# Schematic.net
KiCad netlist of a schematic drawn in Altium Designer
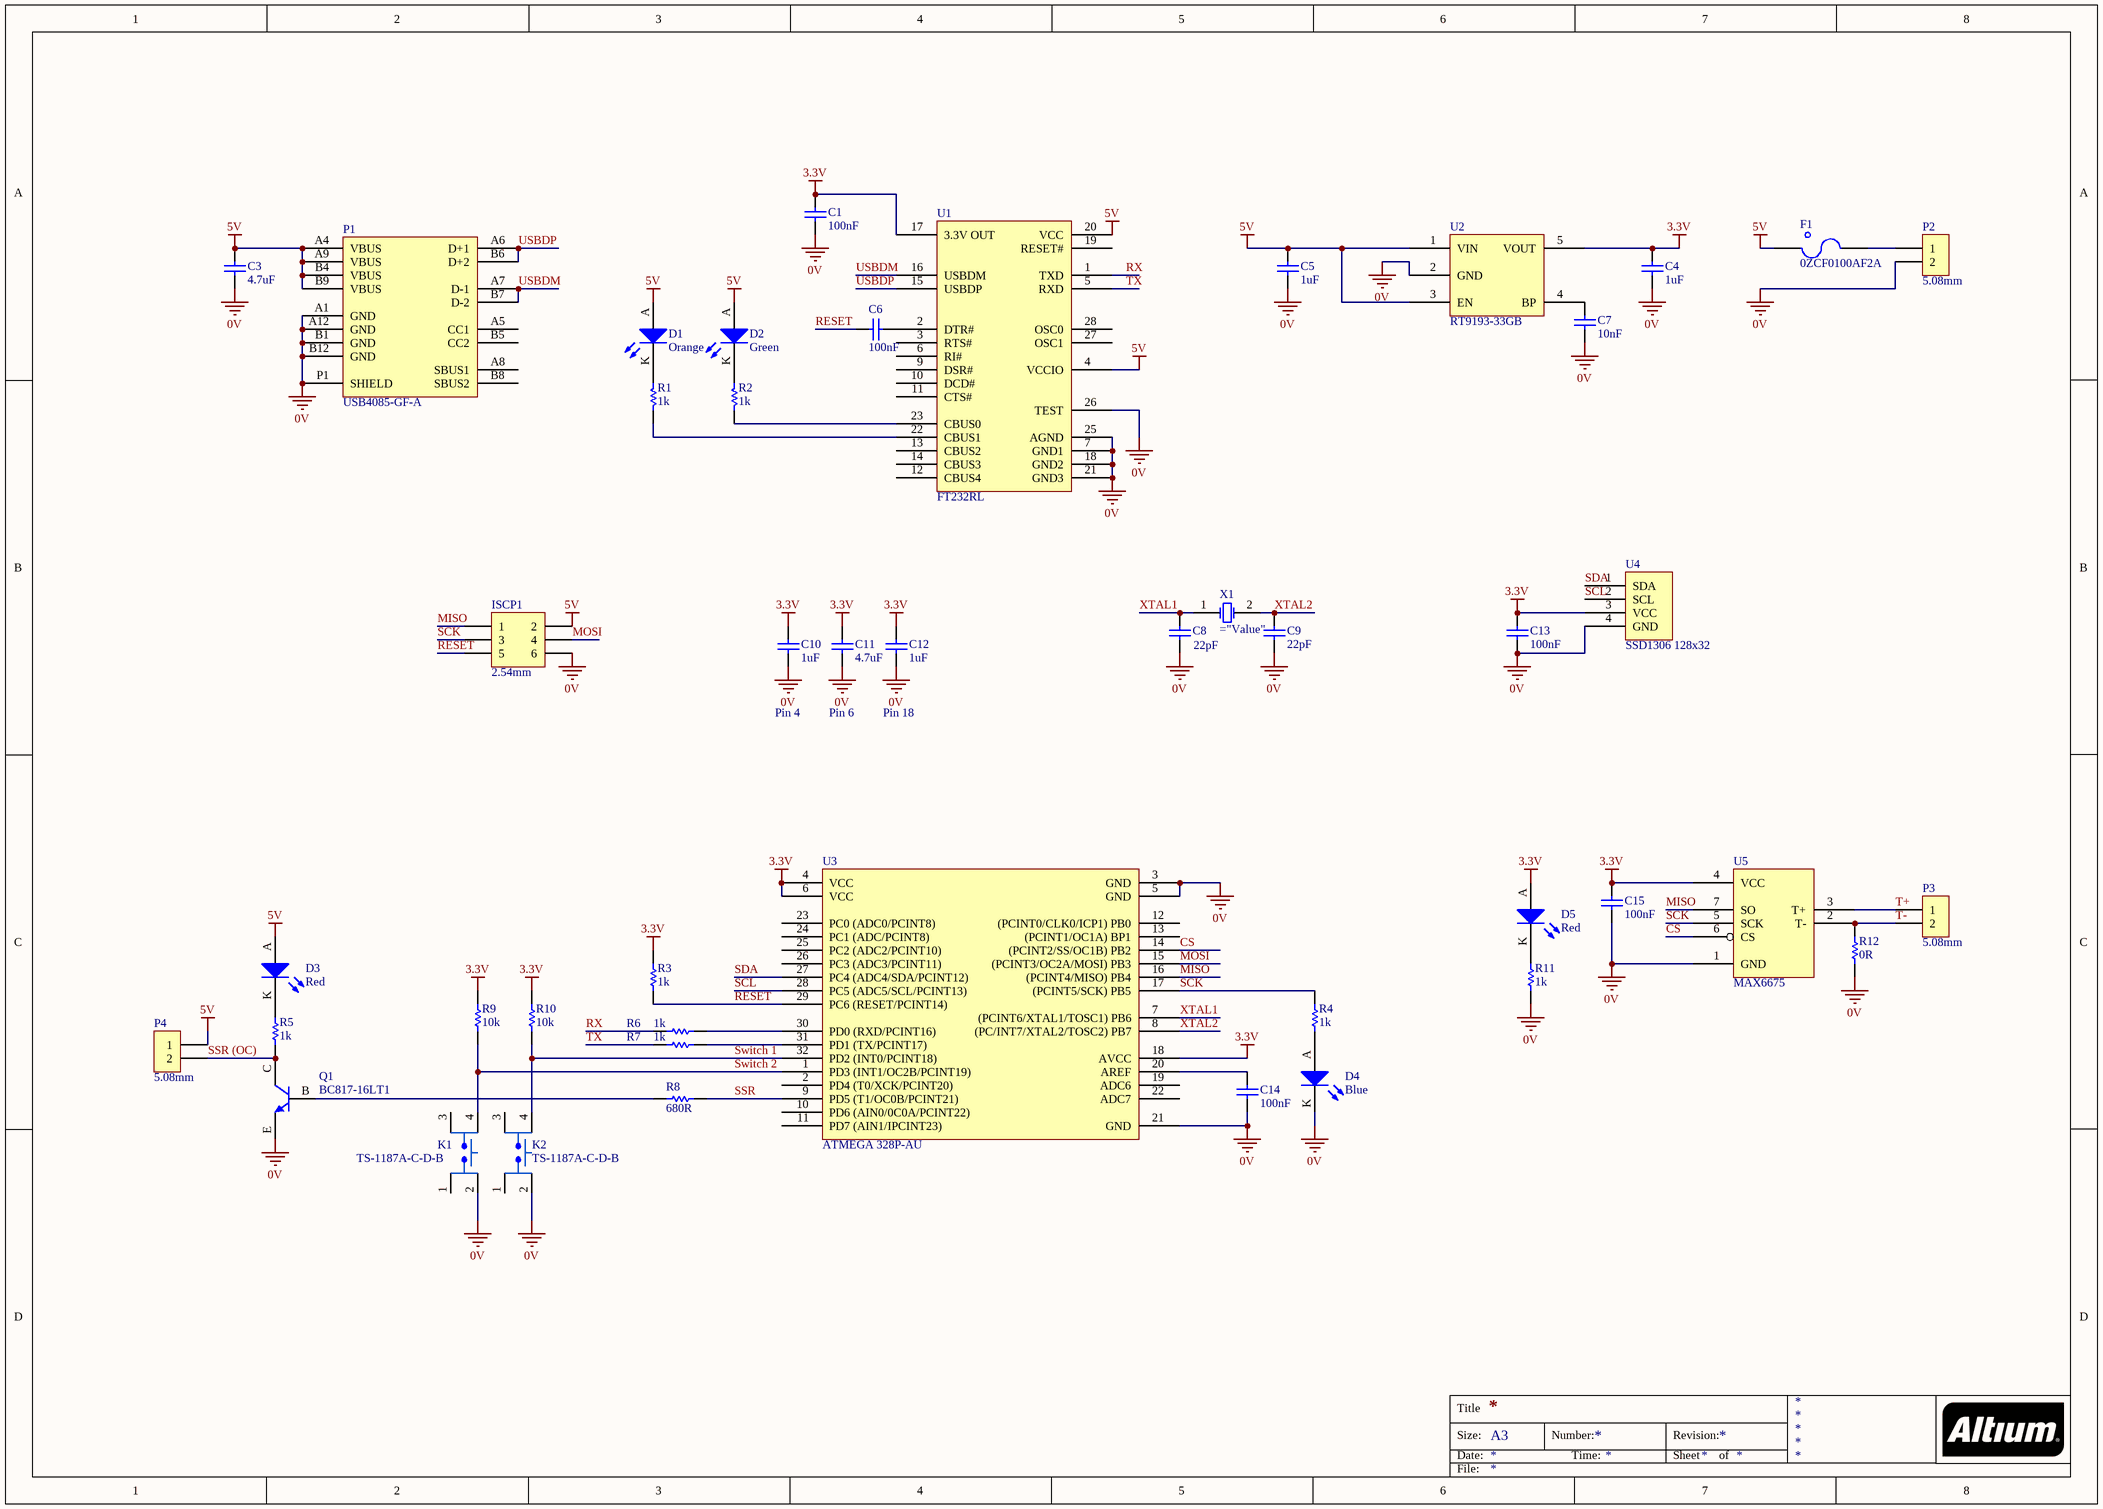
[diagram p0: Schematic.SchDoc]

(export (version "E")
  (design (tool "Eeschema 10.0.6"))
  (components
    (comp (ref "C1")
      (value "100nF")
      (footprint "0805")
      (fields
        (field (name "PART NUMBER") "GCM21BR71H104KA37L")
        (field (name "TOLERANCE") "±10%")
        (field (name "MANUFACTURER") "muRata")
      )
      (libsource (lib "ts_20-standard-library") (part "Capacitor"))
    )
    (comp (ref "C3")
      (value "4.7uF")
      (footprint "0805")
      (fields
        (field (name "PART NUMBER") "GCM21BR61A475KA37L")
        (field (name "TOLERANCE") "10%")
        (field (name "MANUFACTURER") "muRata")
      )
      (libsource (lib "ts_20-standard-library") (part "Capacitor"))
    )
    (comp (ref "C4")
      (value "1uF")
      (footprint "0805")
      (fields
        (field (name "PART NUMBER") "AC0805KKX7R8BB105")
        (field (name "TOLERANCE") "10%")
        (field (name "MANUFACTURER") "YAGEO")
      )
      (libsource (lib "ts_20-standard-library") (part "Capacitor"))
    )
    (comp (ref "C5")
      (value "1uF")
      (footprint "0805")
      (fields
        (field (name "PART NUMBER") "AC0805KKX7R8BB105")
        (field (name "TOLERANCE") "10%")
        (field (name "MANUFACTURER") "YAGEO")
      )
      (libsource (lib "ts_20-standard-library") (part "Capacitor"))
    )
    (comp (ref "C6")
      (value "100nF")
      (footprint "0805")
      (fields
        (field (name "PART NUMBER") "GCM21BR71H104KA37L")
        (field (name "TOLERANCE") "±10%")
        (field (name "MANUFACTURER") "muRata")
      )
      (libsource (lib "ts_20-standard-library") (part "Capacitor"))
    )
    (comp (ref "C7")
      (value "10nF")
      (footprint "0805")
      (fields
        (field (name "PART NUMBER") "GCM2195C1H103JA16D")
        (field (name "TOLERANCE") "±5%")
        (field (name "MANUFACTURER") "muRata")
      )
      (libsource (lib "ts_20-standard-library") (part "Capacitor"))
    )
    (comp (ref "C8")
      (value "22pF")
      (footprint "0805")
      (fields
        (field (name "PART NUMBER") "GRM21A5C2E220JW01D")
        (field (name "TOLERANCE") "±5%")
        (field (name "MANUFACTURER") "muRata")
      )
      (libsource (lib "ts_20-standard-library") (part "Capacitor"))
    )
    (comp (ref "C9")
      (value "22pF")
      (footprint "0805")
      (fields
        (field (name "PART NUMBER") "GRM21A5C2E220JW01D")
        (field (name "TOLERANCE") "±5%")
        (field (name "MANUFACTURER") "muRata")
      )
      (libsource (lib "ts_20-standard-library") (part "Capacitor"))
    )
    (comp (ref "C10")
      (value "1uF")
      (footprint "0805")
      (fields
        (field (name "PART NUMBER") "AC0805KKX7R8BB105")
        (field (name "TOLERANCE") "10%")
        (field (name "MANUFACTURER") "YAGEO")
      )
      (libsource (lib "ts_20-standard-library") (part "Capacitor"))
    )
    (comp (ref "C11")
      (value "4.7uF")
      (footprint "0805")
      (fields
        (field (name "PART NUMBER") "GCM21BR61A475KA37L")
        (field (name "TOLERANCE") "10%")
        (field (name "MANUFACTURER") "muRata")
      )
      (libsource (lib "ts_20-standard-library") (part "Capacitor"))
    )
    (comp (ref "C12")
      (value "1uF")
      (footprint "0805")
      (fields
        (field (name "PART NUMBER") "AC0805KKX7R8BB105")
        (field (name "TOLERANCE") "10%")
        (field (name "MANUFACTURER") "YAGEO")
      )
      (libsource (lib "ts_20-standard-library") (part "Capacitor"))
    )
    (comp (ref "C13")
      (value "100nF")
      (footprint "0805")
      (fields
        (field (name "PART NUMBER") "GCM21BR71H104KA37L")
        (field (name "TOLERANCE") "±10%")
        (field (name "MANUFACTURER") "muRata")
      )
      (libsource (lib "ts_20-standard-library") (part "Capacitor"))
    )
    (comp (ref "C14")
      (value "100nF")
      (footprint "0805")
      (fields
        (field (name "PART NUMBER") "GCM21BR71H104KA37L")
        (field (name "TOLERANCE") "±10%")
        (field (name "MANUFACTURER") "muRata")
      )
      (libsource (lib "ts_20-standard-library") (part "Capacitor"))
    )
    (comp (ref "C15")
      (value "100nF")
      (footprint "0805")
      (fields
        (field (name "PART NUMBER") "GCM21BR71H104KA37L")
        (field (name "TOLERANCE") "±10%")
        (field (name "MANUFACTURER") "muRata")
      )
      (libsource (lib "ts_20-standard-library") (part "Capacitor"))
    )
    (comp (ref "D1")
      (value "Orange")
      (footprint "0805 LED")
      (description "Orange LED Indication - Discrete 1.75V 0805 (2012 Metric)")
      (fields (field (name "PART NUMBER") "SML-211DTT86") (field (name "MANUFACTURER") "ROHM Semiconductor"))
      (libsource (lib "ts_20-standard-library") (part "LED"))
    )
    (comp (ref "D2")
      (value "Green")
      (footprint "0805 LED")
      (description "Green LED Indication - Discrete 1.75V 0805 (2012 Metric)")
      (fields (field (name "PART NUMBER") "SML-210FTT86") (field (name "MANUFACTURER") "ROHM Semiconductor"))
      (libsource (lib "ts_20-standard-library") (part "LED"))
    )
    (comp (ref "D3")
      (value "Red")
      (footprint "0805 LED")
      (description "Red LED Indication - Discrete 1.75V 0805 (2012 Metric)")
      (fields (field (name "PART NUMBER") "SML-210LTT86") (field (name "MANUFACTURER") "ROHM Semiconductor"))
      (libsource (lib "ts_20-standard-library") (part "LED"))
    )
    (comp (ref "D4")
      (value "Blue")
      (footprint "0805 LED")
      (description "LED BLUE CLEAR 2012 SMD")
      (fields
        (field (name "PART NUMBER") "SML-MN2BCTT86C")
        (field (name "MANUFACTURER") "ROHM Semiconductor")
      )
      (libsource (lib "ts_20-standard-library") (part "LED"))
    )
    (comp (ref "D5")
      (value "Red")
      (footprint "0805 LED")
      (description "Red LED Indication - Discrete 1.75V 0805 (2012 Metric)")
      (fields (field (name "PART NUMBER") "SML-210LTT86") (field (name "MANUFACTURER") "ROHM Semiconductor"))
      (libsource (lib "ts_20-standard-library") (part "LED"))
    )
    (comp (ref "F1")
      (value "0ZCF0100AF2A")
      (footprint "2920")
      (description "PTC RESET FUSE 60V 1A 292")
      (fields
        (field (name "MANUFACTURER") "Littelfuse Inc.")
        (field (name "DIGIKEY PART NUMBER") "507-2070-1-ND")
      )
      (libsource (lib "ts_20-standard-library") (part "PTC Fuse"))
    )
    (comp (ref "ISCP1")
      (value "2.54mm")
      (footprint "TH 2.54mm Header 2x3")
      (fields (field (name "PART NUMBER") "TH 2.54mm Header 2x3") (field (name "CONTACT") "NA"))
      (libsource (lib "ts_20-standard-connectors") (part "Header 2x3"))
    )
    (comp (ref "K1")
      (value "TS-1187A-C-D-B")
      (footprint "XKB SW-4.5")
      (description "TACTILE SWITCHES SPST 5.10MM X 5.10MM 0.80MM SMD ROHS")
      (fields (field (name "MANUFACTURER") "XKB Enerprise"))
      (libsource (lib "ts_20-standard-library") (part "SPST (Mom) Push Button"))
    )
    (comp (ref "K2")
      (value "TS-1187A-C-D-B")
      (footprint "XKB SW-4.5")
      (description "TACTILE SWITCHES SPST 5.10MM X 5.10MM 0.80MM SMD ROHS")
      (fields (field (name "MANUFACTURER") "XKB Enerprise"))
      (libsource (lib "ts_20-standard-library") (part "SPST (Mom) Push Button"))
    )
    (comp (ref "P1")
      (value "USB4085-GF-A")
      (footprint "USB4085-GF-A")
      (description "USB - C (Type - C) USB 2.0 Receptacle Connector 16 Position Through Hole, Right Angle")
      (fields (field (name "DIGIKEY PART NUMBER") "2073-USB4085-GF-ACT-ND"))
      (libsource (lib "ts_20-standard-connectors") (part "USB4085-GF-A"))
    )
    (comp (ref "P2")
      (value "5.08mm")
      (footprint "TH 5.08mm Header 1x2")
      (fields
        (field (name "PART NUMBER") "1760510000")
        (field (name "DIGIKEY PART NUMBER") "281-1882-ND")
        (field (name "CONTACT") "NA")
      )
      (libsource (lib "ts_20-standard-connectors") (part "Header 1x2"))
    )
    (comp (ref "P3")
      (value "5.08mm")
      (footprint "TH 5.08mm Header 1x2")
      (fields
        (field (name "PART NUMBER") "1760510000")
        (field (name "DIGIKEY PART NUMBER") "281-1882-ND")
        (field (name "CONTACT") "NA")
      )
      (libsource (lib "ts_20-standard-connectors") (part "Header 1x2"))
    )
    (comp (ref "P4")
      (value "5.08mm")
      (footprint "TH 5.08mm Header 1x2")
      (fields
        (field (name "PART NUMBER") "1760510000")
        (field (name "DIGIKEY PART NUMBER") "281-1882-ND")
        (field (name "CONTACT") "NA")
      )
      (libsource (lib "") (part "Header 1x2_1"))
    )
    (comp (ref "Q1")
      (value "BC817-16LT1")
      (footprint "ON SOT-23 BJT")
      (description "300mW  BJT NPN Transistor")
      (fields
        (field (name "MANUFACTURER") "ON Semiconductor")
        (field (name "DIGIKEY PART NUMBER") "BC817-16LT1OSTR-ND")
      )
      (libsource (lib "ts_20-standard-library") (part "NPN"))
    )
    (comp (ref "R1")
      (value "1k")
      (footprint "0805")
      (fields
        (field (name "PART NUMBER") "RC0805FR071KL")
        (field (name "MANUFACTURER") "YAGEO")
        (field (name "TOLERANCE") "0.01")
      )
      (libsource (lib "ts_20-standard-library") (part "Resistor"))
    )
    (comp (ref "R2")
      (value "1k")
      (footprint "0805")
      (fields
        (field (name "PART NUMBER") "RC0805FR071KL")
        (field (name "MANUFACTURER") "YAGEO")
        (field (name "TOLERANCE") "0.01")
      )
      (libsource (lib "ts_20-standard-library") (part "Resistor"))
    )
    (comp (ref "R3")
      (value "1k")
      (footprint "0805")
      (fields
        (field (name "PART NUMBER") "RC0805FR071KL")
        (field (name "MANUFACTURER") "YAGEO")
        (field (name "TOLERANCE") "0.01")
      )
      (libsource (lib "ts_20-standard-library") (part "Resistor"))
    )
    (comp (ref "R4")
      (value "1k")
      (footprint "0805")
      (fields
        (field (name "PART NUMBER") "RC0805FR071KL")
        (field (name "MANUFACTURER") "YAGEO")
        (field (name "TOLERANCE") "0.01")
      )
      (libsource (lib "ts_20-standard-library") (part "Resistor"))
    )
    (comp (ref "R5")
      (value "1k")
      (footprint "0805")
      (fields
        (field (name "PART NUMBER") "RC0805FR071KL")
        (field (name "MANUFACTURER") "YAGEO")
        (field (name "TOLERANCE") "0.01")
      )
      (libsource (lib "ts_20-standard-library") (part "Resistor"))
    )
    (comp (ref "R6")
      (value "1k")
      (footprint "0805")
      (fields
        (field (name "PART NUMBER") "RC0805FR071KL")
        (field (name "MANUFACTURER") "YAGEO")
        (field (name "TOLERANCE") "0.01")
      )
      (libsource (lib "ts_20-standard-library") (part "Resistor"))
    )
    (comp (ref "R7")
      (value "1k")
      (footprint "0805")
      (fields
        (field (name "PART NUMBER") "RC0805FR071KL")
        (field (name "MANUFACTURER") "YAGEO")
        (field (name "TOLERANCE") "0.01")
      )
      (libsource (lib "ts_20-standard-library") (part "Resistor"))
    )
    (comp (ref "R8")
      (value "680R")
      (footprint "0805")
      (fields
        (field (name "PART NUMBER") "RC0805FR07680RL")
        (field (name "MANUFACTURER") "YAGEO")
        (field (name "TOLERANCE") "0.01")
      )
      (libsource (lib "ts_20-standard-library") (part "Resistor"))
    )
    (comp (ref "R9")
      (value "10k")
      (footprint "0805")
      (fields
        (field (name "PART NUMBER") "RC0805FR0710KL")
        (field (name "MANUFACTURER") "YAGEO")
        (field (name "TOLERANCE") "0.01")
      )
      (libsource (lib "ts_20-standard-library") (part "Resistor"))
    )
    (comp (ref "R10")
      (value "10k")
      (footprint "0805")
      (fields
        (field (name "PART NUMBER") "RC0805FR0710KL")
        (field (name "MANUFACTURER") "YAGEO")
        (field (name "TOLERANCE") "0.01")
      )
      (libsource (lib "ts_20-standard-library") (part "Resistor"))
    )
    (comp (ref "R11")
      (value "1k")
      (footprint "0805")
      (fields
        (field (name "PART NUMBER") "RC0805FR071KL")
        (field (name "MANUFACTURER") "YAGEO")
        (field (name "TOLERANCE") "0.01")
      )
      (libsource (lib "ts_20-standard-library") (part "Resistor"))
    )
    (comp (ref "R12")
      (value "0R")
      (footprint "0805")
      (fields
        (field (name "PART NUMBER") "RC0805FR070RL")
        (field (name "MANUFACTURER") "YAGEO")
        (field (name "TOLERANCE") "0.01")
      )
      (libsource (lib "ts_20-standard-library") (part "Resistor"))
    )
    (comp (ref "U1")
      (value "FT232RL")
      (footprint "FTDI 28-SSOP")
      (description "USB Bridge, USB to UART USB 2.0 UART Interface 28-SSOP")
      (fields (field (name "MANUFACTURER") "FTDI") (field (name "DIGIKEY PART NUMBER") "768-1007-1-ND"))
      (libsource (lib "ts_20-standard-library") (part "FT232RL"))
    )
    (comp (ref "U2")
      (value "RT9193-33GB")
      (footprint "RICHTEK SOT-23-5")
      (description "IC REG LINEAR 3.3V 300MA SOT23-5")
      (fields (field (name "MANUFACTURER") "Richtek") (field (name "DIGIKEY PART NUMBER") "1028-1014-1-ND"))
      (libsource (lib "ts_20-standard-library") (part "RT9193-33GB"))
    )
    (comp (ref "U3")
      (value "ATMEGA 328P-AU")
      (footprint "ATMEL TQFP-32")
      (description "AVR AVR® ATmega Microcontroller IC 8-Bit 20MHz 32KB (16K x 16) FLASH 32-TQFP (7x7)")
      (fields (field (name "MANUFACTURER") "ATMEL") (field (name "DIGIKEY PART NUMBER") "ATMEGA328P-AU-ND"))
      (libsource (lib "ts_20-standard-library") (part "ATMEGA 328P-AU"))
    )
    (comp (ref "U4")
      (value "SSD1306 128x32")
      (footprint "IIC 128x32 OLED")
      (description "AU 0.91\" IIC I2C OLED LCD Display Module 128x32 for Arduino PIC SSD1306 3.3V~5V")
      (fields (field (name "MANUFACTURER") "IIC"))
      (libsource (lib "ts_20-standard-library") (part "SSD1306"))
    )
    (comp (ref "U5")
      (value "MAX6675")
      (footprint "MI 8-SOIC")
      (description "IC THERMOCOUP TO DGTL 8-SOIC")
      (fields
        (field (name "MANUFACTURER") "Maxim Integrated")
        (field (name "DIGIKEY PART NUMBER") "MAX6675ISA+-ND")
      )
      (libsource (lib "ts_20-standard-library") (part "MAX6675"))
    )
    (comp (ref "X1")
      (value "~")
      (footprint "Abracon HC-49/US")
      (fields
        (field (name "PART NUMBER") "ABLS-16.000MHZ-B4-T")
        (field (name "MANUFACTURER") "Abracon LLC")
        (field (name "DIGIKEY PART NUMBER") "535-10226-1-ND")
      )
      (libsource (lib "ts_20-standard-library") (part "Crystal"))
    )
  )
  (nets
    (net (code "1") (name "/CS") (class "Default")
      (node (ref "U3") (pin "14") (pinfunction "(PCINT2/SS/OC1B)_PB2_14") (pintype "passive"))
      (node (ref "U5") (pin "6") (pinfunction "CS_6") (pintype "power_in"))
    )
    (net (code "2") (name "/MISO") (class "Default")
      (node (ref "ISCP1") (pin "1") (pinfunction "1_1") (pintype "passive"))
      (node (ref "U3") (pin "16") (pinfunction "(PCINT4/MISO)_PB4_16") (pintype "passive"))
      (node (ref "U5") (pin "7") (pinfunction "SO_7") (pintype "power_in"))
    )
    (net (code "3") (name "/MOSI") (class "Default")
      (node (ref "ISCP1") (pin "4") (pinfunction "4_4") (pintype "passive"))
      (node (ref "U3") (pin "15") (pinfunction "(PCINT3/OC2A/MOSI)_PB3_15") (pintype "passive"))
    )
    (net (code "4") (name "/RESET") (class "Default")
      (node (ref "C6") (pin "1") (pinfunction "1_1") (pintype "passive"))
      (node (ref "ISCP1") (pin "5") (pinfunction "5_5") (pintype "passive"))
      (node (ref "R3") (pin "1") (pinfunction "1_1") (pintype "passive"))
      (node (ref "U3") (pin "29") (pinfunction "PC6_(RESET/PCINT14)_29") (pintype "passive"))
    )
    (net (code "5") (name "/RX") (class "Default")
      (node (ref "R6") (pin "2") (pinfunction "2_2") (pintype "passive"))
      (node (ref "U1") (pin "1") (pinfunction "TXD_1") (pintype "power_in"))
    )
    (net (code "6") (name "/SCK") (class "Default")
      (node (ref "ISCP1") (pin "3") (pinfunction "3_3") (pintype "passive"))
      (node (ref "R4") (pin "2") (pinfunction "2_2") (pintype "passive"))
      (node (ref "U3") (pin "17") (pinfunction "(PCINT5/SCK)_PB5_17") (pintype "passive"))
      (node (ref "U5") (pin "5") (pinfunction "SCK_5") (pintype "power_in"))
    )
    (net (code "7") (name "/SCL") (class "Default")
      (node (ref "U3") (pin "28") (pinfunction "PC5_(ADC5/SCL/PCINT13)_28") (pintype "passive"))
      (node (ref "U4") (pin "2") (pinfunction "SCL_2") (pintype "passive"))
    )
    (net (code "8") (name "/SDA") (class "Default")
      (node (ref "U3") (pin "27") (pinfunction "PC4_(ADC4/SDA/PCINT12)_27") (pintype "passive"))
      (node (ref "U4") (pin "1") (pinfunction "SDA_1") (pintype "passive"))
    )
    (net (code "9") (name "/SSR") (class "Default")
      (node (ref "R8") (pin "2") (pinfunction "2_2") (pintype "passive"))
      (node (ref "U3") (pin "9") (pinfunction "PD5_(T1/OC0B/PCINT21)_9") (pintype "passive"))
    )
    (net (code "10") (name "/SSR (OC)") (class "Default")
      (node (ref "P4") (pin "2") (pinfunction "2_2") (pintype "passive"))
      (node (ref "Q1") (pin "C") (pinfunction "C_C") (pintype "passive"))
      (node (ref "R5") (pin "1") (pinfunction "1_1") (pintype "passive"))
    )
    (net (code "11") (name "/Switch 1") (class "Default")
      (node (ref "K2") (pin "4") (pinfunction "VDD_4") (pintype "passive"))
      (node (ref "R10") (pin "1") (pinfunction "1_1") (pintype "passive"))
      (node (ref "U3") (pin "32") (pinfunction "PD2_(INT0/PCINT18)_32") (pintype "passive"))
    )
    (net (code "12") (name "/Switch 2") (class "Default")
      (node (ref "K1") (pin "4") (pinfunction "VDD_4") (pintype "passive"))
      (node (ref "R9") (pin "1") (pinfunction "1_1") (pintype "passive"))
      (node (ref "U3") (pin "1") (pinfunction "PD3_(INT1/OC2B/PCINT19)_1") (pintype "passive"))
    )
    (net (code "13") (name "/T+") (class "Default")
      (node (ref "P3") (pin "1") (pinfunction "1_1") (pintype "passive"))
      (node (ref "U5") (pin "3") (pinfunction "T+_3") (pintype "power_in"))
    )
    (net (code "14") (name "/T-") (class "Default")
      (node (ref "P3") (pin "2") (pinfunction "2_2") (pintype "passive"))
      (node (ref "R12") (pin "2") (pinfunction "2_2") (pintype "passive"))
      (node (ref "U5") (pin "2") (pinfunction "T-_2") (pintype "power_in"))
    )
    (net (code "15") (name "/TX") (class "Default")
      (node (ref "R7") (pin "2") (pinfunction "2_2") (pintype "passive"))
      (node (ref "U1") (pin "5") (pinfunction "RXD_5") (pintype "power_in"))
    )
    (net (code "16") (name "/USBDM") (class "Default")
      (node (ref "P1") (pin "A7") (pinfunction "D-1_A7") (pintype "passive"))
      (node (ref "P1") (pin "B7") (pinfunction "D-2_B7") (pintype "passive"))
      (node (ref "U1") (pin "16") (pinfunction "USBDM_16") (pintype "power_in"))
    )
    (net (code "17") (name "/USBDP") (class "Default")
      (node (ref "P1") (pin "A6") (pinfunction "D+1_A6") (pintype "passive"))
      (node (ref "P1") (pin "B6") (pinfunction "D+2_B6") (pintype "passive"))
      (node (ref "U1") (pin "15") (pinfunction "USBDP_15") (pintype "power_in"))
    )
    (net (code "18") (name "/XTAL1") (class "Default")
      (node (ref "C8") (pin "2") (pinfunction "2_2") (pintype "passive"))
      (node (ref "U3") (pin "7") (pinfunction "(PCINT6/XTAL1/TOSC1)_PB6_7") (pintype "passive"))
      (node (ref "X1") (pin "1") (pinfunction "OSC1_1") (pintype "passive"))
    )
    (net (code "19") (name "/XTAL2") (class "Default")
      (node (ref "C9") (pin "2") (pinfunction "2_2") (pintype "passive"))
      (node (ref "U3") (pin "8") (pinfunction "(PC/INT7/XTAL2/TOSC2)_PB7_8") (pintype "passive"))
      (node (ref "X1") (pin "2") (pinfunction "OSC2_2") (pintype "passive"))
    )
    (net (code "20") (name "0V") (class "Default")
      (node (ref "C1") (pin "2") (pinfunction "2_2") (pintype "passive"))
      (node (ref "C10") (pin "1") (pinfunction "1_1") (pintype "passive"))
      (node (ref "C11") (pin "1") (pinfunction "1_1") (pintype "passive"))
      (node (ref "C12") (pin "1") (pinfunction "1_1") (pintype "passive"))
      (node (ref "C13") (pin "1") (pinfunction "1_1") (pintype "passive"))
      (node (ref "C14") (pin "1") (pinfunction "1_1") (pintype "passive"))
      (node (ref "C15") (pin "1") (pinfunction "1_1") (pintype "passive"))
      (node (ref "C3") (pin "1") (pinfunction "1_1") (pintype "passive"))
      (node (ref "C4") (pin "1") (pinfunction "1_1") (pintype "passive"))
      (node (ref "C5") (pin "1") (pinfunction "1_1") (pintype "passive"))
      (node (ref "C7") (pin "1") (pinfunction "1_1") (pintype "passive"))
      (node (ref "C8") (pin "1") (pinfunction "1_1") (pintype "passive"))
      (node (ref "C9") (pin "1") (pinfunction "1_1") (pintype "passive"))
      (node (ref "D4") (pin "K") (pinfunction "K_K") (pintype "passive"))
      (node (ref "ISCP1") (pin "6") (pinfunction "6_6") (pintype "passive"))
      (node (ref "K1") (pin "2") (pinfunction "VDD_2") (pintype "passive"))
      (node (ref "K2") (pin "2") (pinfunction "VDD_2") (pintype "passive"))
      (node (ref "P1") (pin "A1") (pinfunction "GND_A1") (pintype "passive"))
      (node (ref "P1") (pin "A12") (pinfunction "GND_A12") (pintype "passive"))
      (node (ref "P1") (pin "B1") (pinfunction "GND_B1") (pintype "passive"))
      (node (ref "P1") (pin "B12") (pinfunction "GND_B12") (pintype "passive"))
      (node (ref "P1") (pin "P1") (pinfunction "SHIELD_P1") (pintype "passive"))
      (node (ref "P2") (pin "2") (pinfunction "2_2") (pintype "passive"))
      (node (ref "Q1") (pin "E") (pinfunction "E_E") (pintype "passive"))
      (node (ref "R11") (pin "1") (pinfunction "1_1") (pintype "passive"))
      (node (ref "R12") (pin "1") (pinfunction "1_1") (pintype "passive"))
      (node (ref "U1") (pin "18") (pinfunction "GND2_18") (pintype "power_in"))
      (node (ref "U1") (pin "21") (pinfunction "GND3_21") (pintype "power_in"))
      (node (ref "U1") (pin "25") (pinfunction "AGND_25") (pintype "power_in"))
      (node (ref "U1") (pin "26") (pinfunction "TEST_26") (pintype "power_in"))
      (node (ref "U1") (pin "7") (pinfunction "GND1_7") (pintype "power_in"))
      (node (ref "U2") (pin "2") (pinfunction "GND_2") (pintype "passive"))
      (node (ref "U3") (pin "21") (pinfunction "GND_21") (pintype "passive"))
      (node (ref "U3") (pin "3") (pinfunction "GND_3") (pintype "passive"))
      (node (ref "U3") (pin "5") (pinfunction "GND_5") (pintype "passive"))
      (node (ref "U4") (pin "4") (pinfunction "GND_4") (pintype "passive"))
      (node (ref "U5") (pin "1") (pinfunction "GND_1") (pintype "power_in"))
    )
    (net (code "21") (name "3.3V") (class "Default")
      (node (ref "C1") (pin "1") (pinfunction "1_1") (pintype "passive"))
      (node (ref "C10") (pin "2") (pinfunction "2_2") (pintype "passive"))
      (node (ref "C11") (pin "2") (pinfunction "2_2") (pintype "passive"))
      (node (ref "C12") (pin "2") (pinfunction "2_2") (pintype "passive"))
      (node (ref "C13") (pin "2") (pinfunction "2_2") (pintype "passive"))
      (node (ref "C15") (pin "2") (pinfunction "2_2") (pintype "passive"))
      (node (ref "C4") (pin "2") (pinfunction "2_2") (pintype "passive"))
      (node (ref "D5") (pin "A") (pinfunction "A_A") (pintype "passive"))
      (node (ref "R10") (pin "2") (pinfunction "2_2") (pintype "passive"))
      (node (ref "R3") (pin "2") (pinfunction "2_2") (pintype "passive"))
      (node (ref "R9") (pin "2") (pinfunction "2_2") (pintype "passive"))
      (node (ref "U1") (pin "17") (pinfunction "3.3V_OUT_17") (pintype "power_in"))
      (node (ref "U2") (pin "5") (pinfunction "VOUT_5") (pintype "passive"))
      (node (ref "U3") (pin "18") (pinfunction "AVCC_18") (pintype "passive"))
      (node (ref "U3") (pin "4") (pinfunction "VCC_4") (pintype "passive"))
      (node (ref "U3") (pin "6") (pinfunction "VCC_6") (pintype "passive"))
      (node (ref "U4") (pin "3") (pinfunction "VCC_3") (pintype "passive"))
      (node (ref "U5") (pin "4") (pinfunction "VCC_4") (pintype "power_in"))
    )
    (net (code "22") (name "5V") (class "Default")
      (node (ref "C3") (pin "2") (pinfunction "2_2") (pintype "passive"))
      (node (ref "C5") (pin "2") (pinfunction "2_2") (pintype "passive"))
      (node (ref "D1") (pin "A") (pinfunction "A_A") (pintype "passive"))
      (node (ref "D2") (pin "A") (pinfunction "A_A") (pintype "passive"))
      (node (ref "D3") (pin "A") (pinfunction "A_A") (pintype "passive"))
      (node (ref "F1") (pin "2") (pinfunction "2_2") (pintype "passive"))
      (node (ref "ISCP1") (pin "2") (pinfunction "2_2") (pintype "passive"))
      (node (ref "P1") (pin "A4") (pinfunction "VBUS_A4") (pintype "passive"))
      (node (ref "P1") (pin "A9") (pinfunction "VBUS_A9") (pintype "passive"))
      (node (ref "P1") (pin "B4") (pinfunction "VBUS_B4") (pintype "passive"))
      (node (ref "P1") (pin "B9") (pinfunction "VBUS_B9") (pintype "passive"))
      (node (ref "P4") (pin "1") (pinfunction "1_1") (pintype "passive"))
      (node (ref "U1") (pin "20") (pinfunction "VCC_20") (pintype "power_in"))
      (node (ref "U1") (pin "4") (pinfunction "VCCIO_4") (pintype "power_in"))
      (node (ref "U2") (pin "1") (pinfunction "VIN_1") (pintype "passive"))
      (node (ref "U2") (pin "3") (pinfunction "EN_3") (pintype "passive"))
    )
    (net (code "23") (name "Net-(D1-PadK)") (class "Default")
      (node (ref "D1") (pin "K") (pinfunction "K_K") (pintype "passive"))
      (node (ref "R1") (pin "1") (pinfunction "1_1") (pintype "passive"))
    )
    (net (code "24") (name "Net-(D2-PadK)") (class "Default")
      (node (ref "D2") (pin "K") (pinfunction "K_K") (pintype "passive"))
      (node (ref "R2") (pin "1") (pinfunction "1_1") (pintype "passive"))
    )
    (net (code "25") (name "Net-(D3-PadK)") (class "Default")
      (node (ref "D3") (pin "K") (pinfunction "K_K") (pintype "passive"))
      (node (ref "R5") (pin "2") (pinfunction "2_2") (pintype "passive"))
    )
    (net (code "26") (name "Net-(D4-PadA)") (class "Default")
      (node (ref "D4") (pin "A") (pinfunction "A_A") (pintype "passive"))
      (node (ref "R4") (pin "1") (pinfunction "1_1") (pintype "passive"))
    )
    (net (code "27") (name "Net-(D5-PadK)") (class "Default")
      (node (ref "D5") (pin "K") (pinfunction "K_K") (pintype "passive"))
      (node (ref "R11") (pin "2") (pinfunction "2_2") (pintype "passive"))
    )
    (net (code "28") (name "Net-(F1-Pad1)") (class "Default")
      (node (ref "F1") (pin "1") (pinfunction "1_1") (pintype "passive"))
      (node (ref "P2") (pin "1") (pinfunction "1_1") (pintype "passive"))
    )
    (net (code "29") (name "Net-(Q1-PadB)") (class "Default")
      (node (ref "Q1") (pin "B") (pinfunction "B_B") (pintype "passive"))
      (node (ref "R8") (pin "1") (pinfunction "1_1") (pintype "passive"))
    )
    (net (code "30") (name "Net-(U1-CBUS0)") (class "Default")
      (node (ref "R2") (pin "2") (pinfunction "2_2") (pintype "passive"))
      (node (ref "U1") (pin "23") (pinfunction "CBUS0_23") (pintype "power_in"))
    )
    (net (code "31") (name "Net-(U1-CBUS1)") (class "Default")
      (node (ref "R1") (pin "2") (pinfunction "2_2") (pintype "passive"))
      (node (ref "U1") (pin "22") (pinfunction "CBUS1_22") (pintype "power_in"))
    )
    (net (code "32") (name "Net-(U1-DTR#)") (class "Default")
      (node (ref "C6") (pin "2") (pinfunction "2_2") (pintype "passive"))
      (node (ref "U1") (pin "2") (pinfunction "DTR#_2") (pintype "power_in"))
    )
    (net (code "33") (name "Net-(U2-BP)") (class "Default")
      (node (ref "C7") (pin "2") (pinfunction "2_2") (pintype "passive"))
      (node (ref "U2") (pin "4") (pinfunction "BP_4") (pintype "passive"))
    )
    (net (code "34") (name "Net-(U3-AREF)") (class "Default")
      (node (ref "C14") (pin "2") (pinfunction "2_2") (pintype "passive"))
      (node (ref "U3") (pin "20") (pinfunction "AREF_20") (pintype "passive"))
    )
    (net (code "35") (name "Net-(U3-PD0_(RXD{slash}PCINT16))") (class "Default")
      (node (ref "R6") (pin "1") (pinfunction "1_1") (pintype "passive"))
      (node (ref "U3") (pin "30") (pinfunction "PD0_(RXD/PCINT16)_30") (pintype "passive"))
    )
    (net (code "36") (name "Net-(U3-PD1_(TX{slash}PCINT17))") (class "Default")
      (node (ref "R7") (pin "1") (pinfunction "1_1") (pintype "passive"))
      (node (ref "U3") (pin "31") (pinfunction "PD1_(TX/PCINT17)_31") (pintype "passive"))
    )
    (net (code "37") (name "unconnected-(K1-VDD-Pad1)") (class "Default")
      (node (ref "K1") (pin "1") (pinfunction "VDD_1") (pintype "passive"))
    )
    (net (code "38") (name "unconnected-(K1-VDD-Pad3)") (class "Default")
      (node (ref "K1") (pin "3") (pinfunction "VDD_3") (pintype "passive"))
    )
    (net (code "39") (name "unconnected-(K2-VDD-Pad1)") (class "Default")
      (node (ref "K2") (pin "1") (pinfunction "VDD_1") (pintype "passive"))
    )
    (net (code "40") (name "unconnected-(K2-VDD-Pad3)") (class "Default")
      (node (ref "K2") (pin "3") (pinfunction "VDD_3") (pintype "passive"))
    )
    (net (code "41") (name "unconnected-(P1-CC1-PadA5)") (class "Default")
      (node (ref "P1") (pin "A5") (pinfunction "CC1_A5") (pintype "passive"))
    )
    (net (code "42") (name "unconnected-(P1-CC2-PadB5)") (class "Default")
      (node (ref "P1") (pin "B5") (pinfunction "CC2_B5") (pintype "passive"))
    )
    (net (code "43") (name "unconnected-(P1-SBUS1-PadA8)") (class "Default")
      (node (ref "P1") (pin "A8") (pinfunction "SBUS1_A8") (pintype "passive"))
    )
    (net (code "44") (name "unconnected-(P1-SBUS2-PadB8)") (class "Default")
      (node (ref "P1") (pin "B8") (pinfunction "SBUS2_B8") (pintype "passive"))
    )
    (net (code "45") (name "unconnected-(U1-CBUS2-Pad13)") (class "Default")
      (node (ref "U1") (pin "13") (pinfunction "CBUS2_13") (pintype "power_in"))
    )
    (net (code "46") (name "unconnected-(U1-CBUS3-Pad14)") (class "Default")
      (node (ref "U1") (pin "14") (pinfunction "CBUS3_14") (pintype "power_in"))
    )
    (net (code "47") (name "unconnected-(U1-CBUS4-Pad12)") (class "Default")
      (node (ref "U1") (pin "12") (pinfunction "CBUS4_12") (pintype "power_in"))
    )
    (net (code "48") (name "unconnected-(U1-CTS#-Pad11)") (class "Default")
      (node (ref "U1") (pin "11") (pinfunction "CTS#_11") (pintype "power_in"))
    )
    (net (code "49") (name "unconnected-(U1-DCD#-Pad10)") (class "Default")
      (node (ref "U1") (pin "10") (pinfunction "DCD#_10") (pintype "power_in"))
    )
    (net (code "50") (name "unconnected-(U1-DSR#-Pad9)") (class "Default")
      (node (ref "U1") (pin "9") (pinfunction "DSR#_9") (pintype "power_in"))
    )
    (net (code "51") (name "unconnected-(U1-OSC0-Pad28)") (class "Default")
      (node (ref "U1") (pin "28") (pinfunction "OSC0_28") (pintype "power_in"))
    )
    (net (code "52") (name "unconnected-(U1-OSC1-Pad27)") (class "Default")
      (node (ref "U1") (pin "27") (pinfunction "OSC1_27") (pintype "power_in"))
    )
    (net (code "53") (name "unconnected-(U1-RESET#-Pad19)") (class "Default")
      (node (ref "U1") (pin "19") (pinfunction "RESET#_19") (pintype "power_in"))
    )
    (net (code "54") (name "unconnected-(U1-RI#-Pad6)") (class "Default")
      (node (ref "U1") (pin "6") (pinfunction "RI#_6") (pintype "power_in"))
    )
    (net (code "55") (name "unconnected-(U1-RTS#-Pad3)") (class "Default")
      (node (ref "U1") (pin "3") (pinfunction "RTS#_3") (pintype "power_in"))
    )
    (net (code "56") (name "unconnected-(U3-(PCINT0{slash}CLK0{slash}ICP1)_PB0-Pad12)") (class "Default")
      (node (ref "U3") (pin "12") (pinfunction "(PCINT0/CLK0/ICP1)_PB0_12") (pintype "passive"))
    )
    (net (code "57") (name "unconnected-(U3-(PCINT1{slash}OC1A)_BP1-Pad13)") (class "Default")
      (node (ref "U3") (pin "13") (pinfunction "(PCINT1/OC1A)_BP1_13") (pintype "passive"))
    )
    (net (code "58") (name "unconnected-(U3-ADC6-Pad19)") (class "Default")
      (node (ref "U3") (pin "19") (pinfunction "ADC6_19") (pintype "passive"))
    )
    (net (code "59") (name "unconnected-(U3-ADC7-Pad22)") (class "Default")
      (node (ref "U3") (pin "22") (pinfunction "ADC7_22") (pintype "passive"))
    )
    (net (code "60") (name "unconnected-(U3-PC0_(ADC0{slash}PCINT8)-Pad23)") (class "Default")
      (node (ref "U3") (pin "23") (pinfunction "PC0_(ADC0/PCINT8)_23") (pintype "passive"))
    )
    (net (code "61") (name "unconnected-(U3-PC1_(ADC{slash}PCINT8)-Pad24)") (class "Default")
      (node (ref "U3") (pin "24") (pinfunction "PC1_(ADC/PCINT8)_24") (pintype "passive"))
    )
    (net (code "62") (name "unconnected-(U3-PC2_(ADC2{slash}PCINT10)-Pad25)") (class "Default")
      (node (ref "U3") (pin "25") (pinfunction "PC2_(ADC2/PCINT10)_25") (pintype "passive"))
    )
    (net (code "63") (name "unconnected-(U3-PC3_(ADC3{slash}PCINT11)-Pad26)") (class "Default")
      (node (ref "U3") (pin "26") (pinfunction "PC3_(ADC3/PCINT11)_26") (pintype "passive"))
    )
    (net (code "64") (name "unconnected-(U3-PD4_(T0{slash}XCK{slash}PCINT20)-Pad2)") (class "Default")
      (node (ref "U3") (pin "2") (pinfunction "PD4_(T0/XCK/PCINT20)_2") (pintype "passive"))
    )
    (net (code "65") (name "unconnected-(U3-PD6_(AIN0{slash}0C0A{slash}PCINT22)-Pad10)") (class "Default")
      (node (ref "U3") (pin "10") (pinfunction "PD6_(AIN0/0C0A/PCINT22)_10") (pintype "passive"))
    )
    (net (code "66") (name "unconnected-(U3-PD7_(AIN1{slash}IPCINT23)-Pad11)") (class "Default")
      (node (ref "U3") (pin "11") (pinfunction "PD7_(AIN1/IPCINT23)_11") (pintype "passive"))
    )
  )
)
